# pcb_maquina.net
KiCad netlist of a schematic drawn in EAGLE
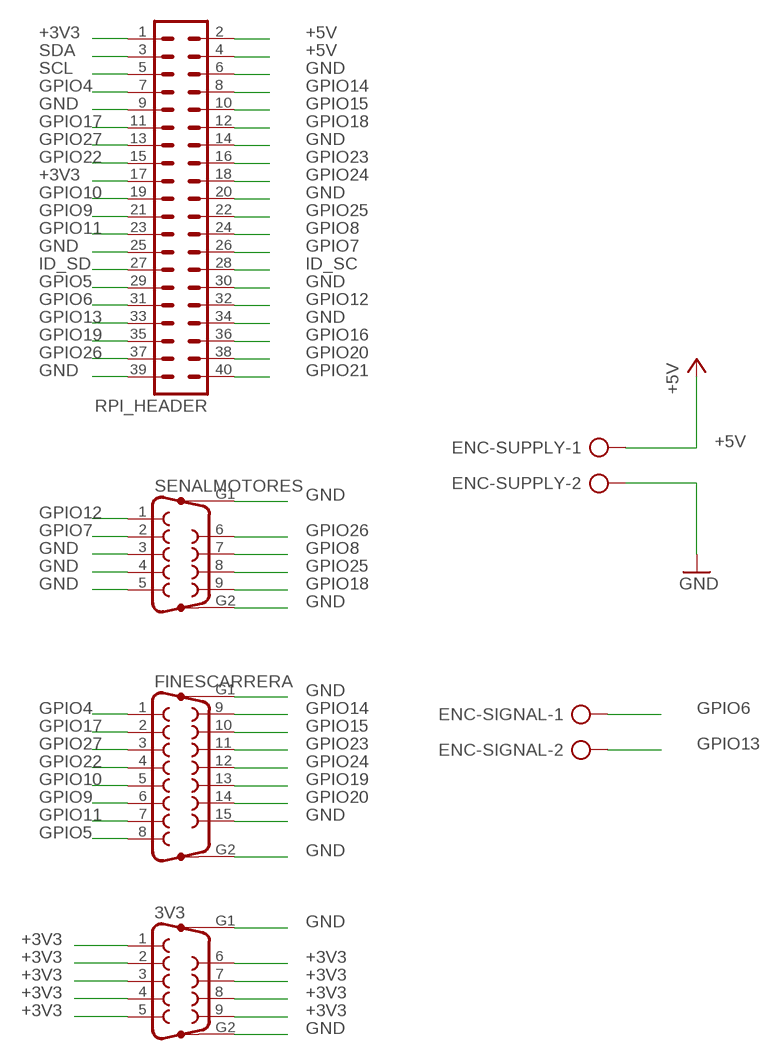
[diagram p0: schematic, sheet 1]
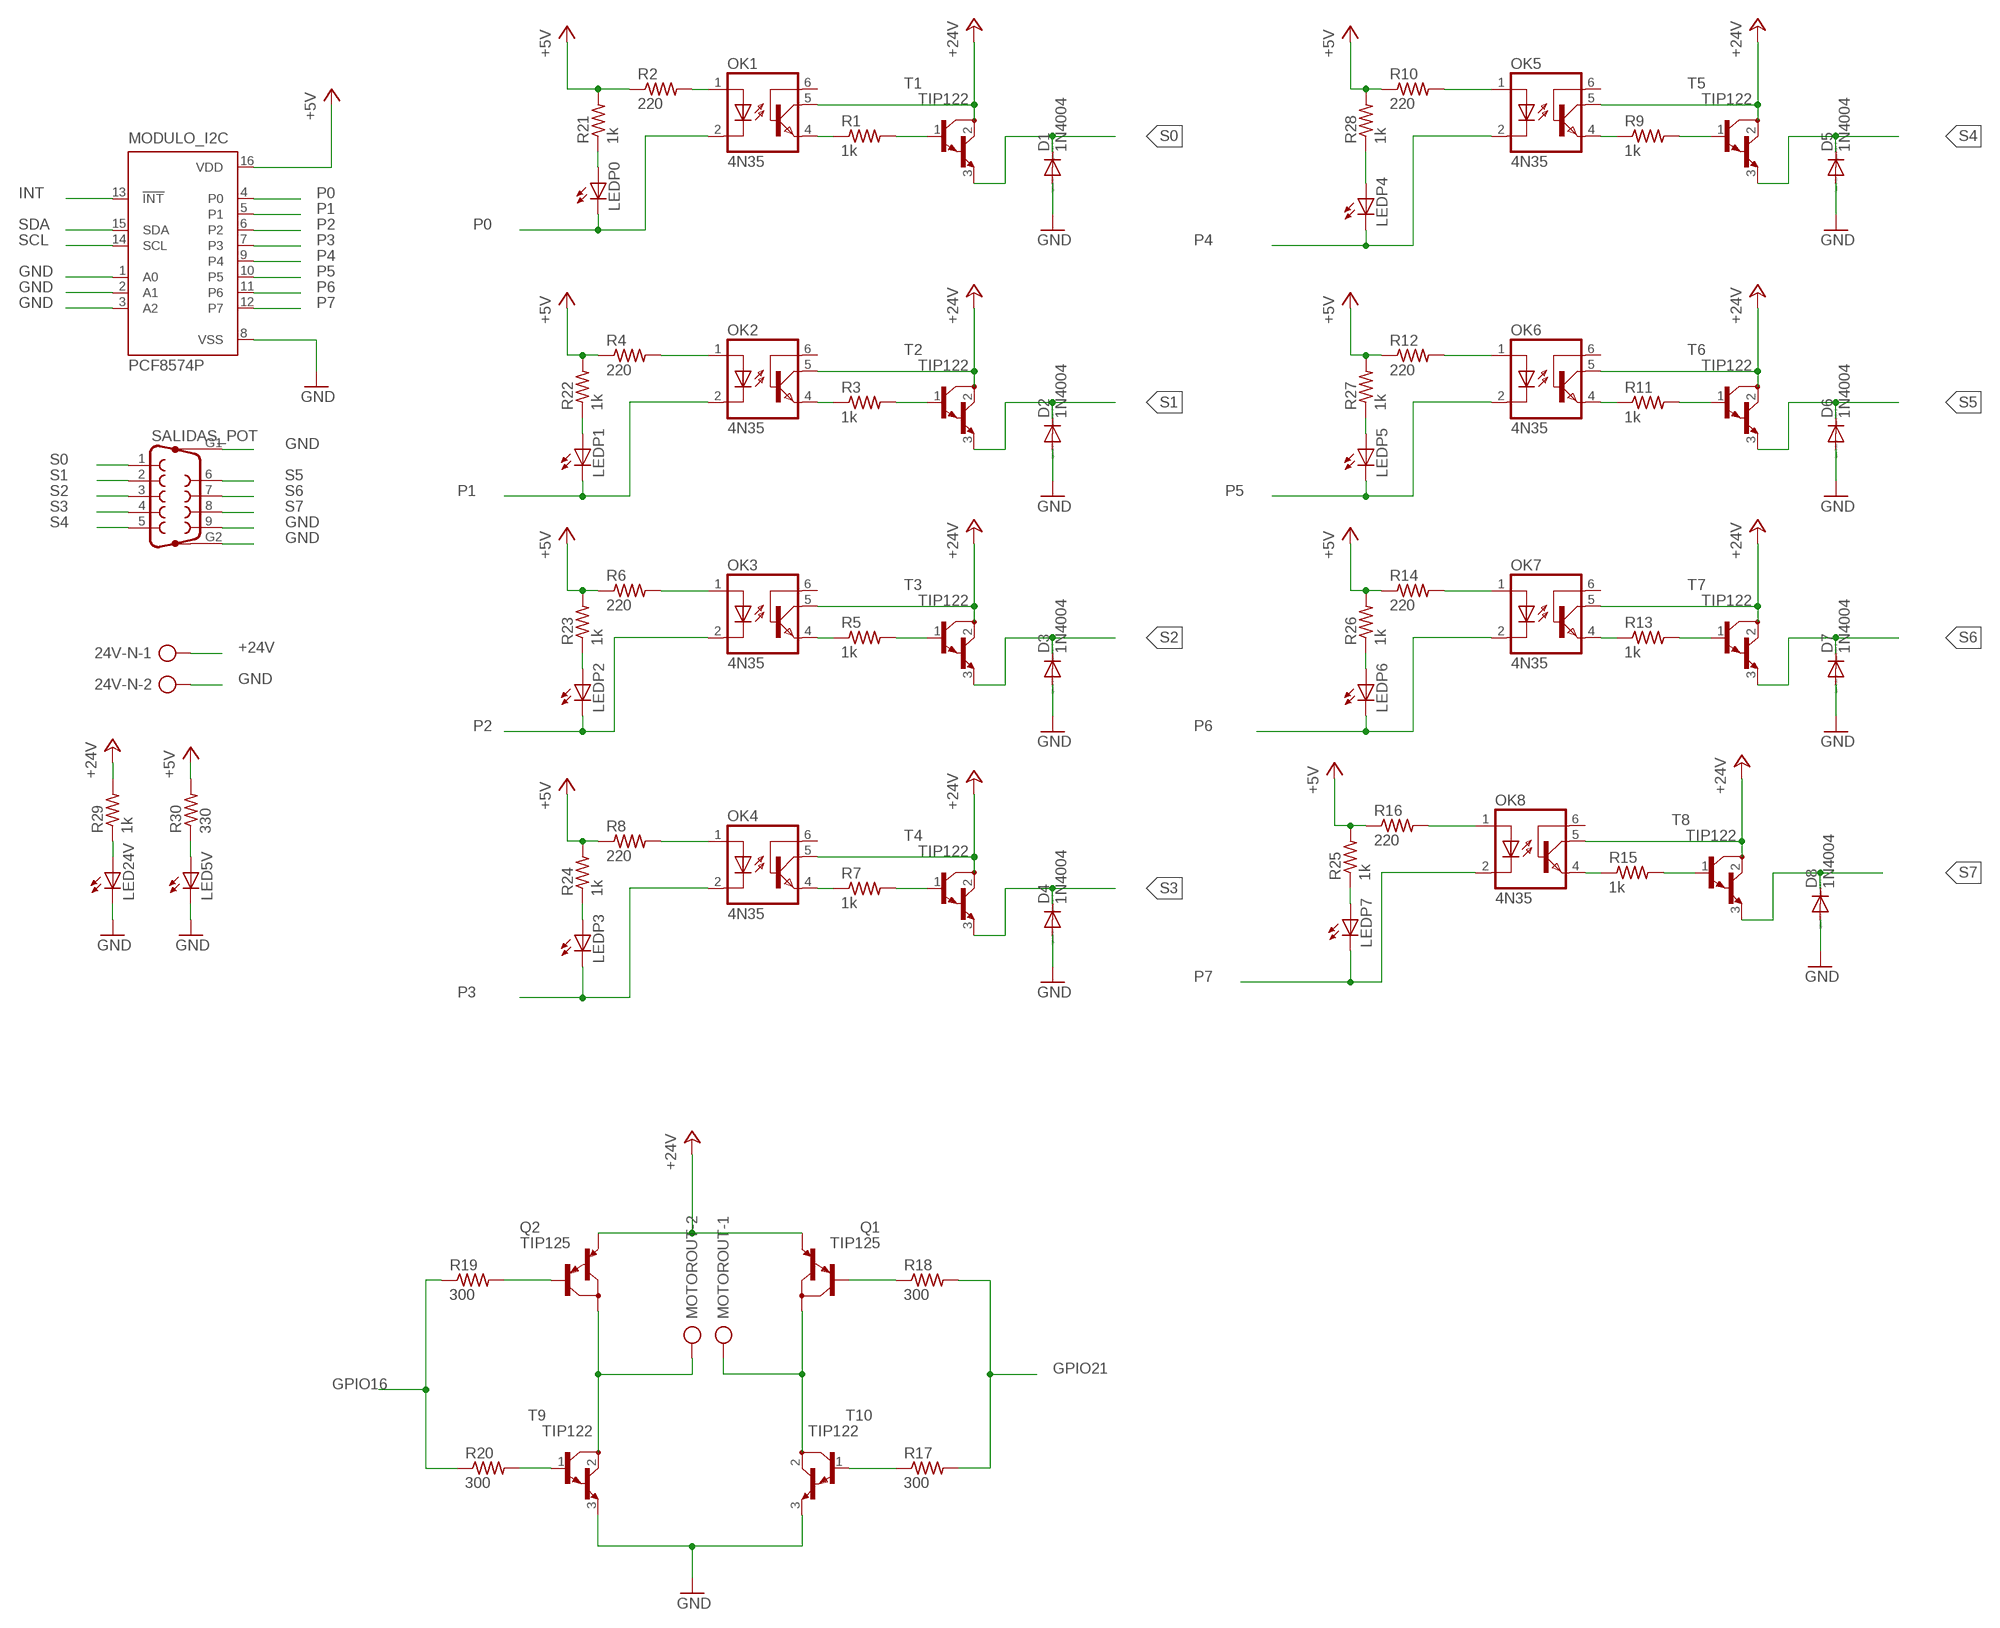
[diagram p1: schematic, sheet 2]

(export (version "E")
  (design (tool "Eeschema 10.0.6"))
  (components
    (comp (ref "3V3")
      (value "F09HP")
      (footprint "eagle-import:F09HP")
      (libsource (lib "eagle-import") (part "F09HP"))
    )
    (comp (ref "ENC-SIGNAL")
      (value "AK500/2")
      (footprint "eagle-import:AK500_2")
      (libsource (lib "eagle-import") (part "AK500/2"))
    )
    (comp (ref "ENC-SUPPLY")
      (value "AK500/2")
      (footprint "eagle-import:AK500_2")
      (libsource (lib "eagle-import") (part "AK500/2"))
    )
    (comp (ref "FINESCARRERA")
      (value "F15HP")
      (footprint "eagle-import:F15HP")
      (libsource (lib "eagle-import") (part "F15HP"))
    )
    (comp (ref "RPI_HEADER")
      (value "MA20-2")
      (footprint "eagle-import:MA20-2")
      (libsource (lib "eagle-import") (part "MA20-2"))
    )
    (comp (ref "SENALMOTORES")
      (value "F09HP")
      (footprint "eagle-import:F09HP")
      (libsource (lib "eagle-import") (part "F09HP"))
    )
    (comp (ref "24V-N")
      (value "AK300/2")
      (footprint "eagle-import:AK300_2")
      (libsource (lib "eagle-import") (part "AK300/2"))
    )
    (comp (ref "D1")
      (value "1N4004")
      (footprint "eagle-import:DO41-10")
      (libsource (lib "eagle-import") (part "1N4004"))
    )
    (comp (ref "D2")
      (value "1N4004")
      (footprint "eagle-import:DO41-10")
      (libsource (lib "eagle-import") (part "1N4004"))
    )
    (comp (ref "D3")
      (value "1N4004")
      (footprint "eagle-import:DO41-10")
      (libsource (lib "eagle-import") (part "1N4004"))
    )
    (comp (ref "D4")
      (value "1N4004")
      (footprint "eagle-import:DO41-10")
      (libsource (lib "eagle-import") (part "1N4004"))
    )
    (comp (ref "D5")
      (value "1N4004")
      (footprint "eagle-import:DO41-10")
      (libsource (lib "eagle-import") (part "1N4004"))
    )
    (comp (ref "D6")
      (value "1N4004")
      (footprint "eagle-import:DO41-10")
      (libsource (lib "eagle-import") (part "1N4004"))
    )
    (comp (ref "D7")
      (value "1N4004")
      (footprint "eagle-import:DO41-10")
      (libsource (lib "eagle-import") (part "1N4004"))
    )
    (comp (ref "D8")
      (value "1N4004")
      (footprint "eagle-import:DO41-10")
      (libsource (lib "eagle-import") (part "1N4004"))
    )
    (comp (ref "LED5V")
      (value "LED3MM")
      (footprint "eagle-import:LED3MM")
      (libsource (lib "eagle-import") (part "LED3MM"))
    )
    (comp (ref "LED24V")
      (value "LED3MM")
      (footprint "eagle-import:LED3MM")
      (libsource (lib "eagle-import") (part "LED3MM"))
    )
    (comp (ref "LEDP0")
      (value "LED3MM")
      (footprint "eagle-import:LED3MM")
      (libsource (lib "eagle-import") (part "LED3MM"))
    )
    (comp (ref "LEDP1")
      (value "LED3MM")
      (footprint "eagle-import:LED3MM")
      (libsource (lib "eagle-import") (part "LED3MM"))
    )
    (comp (ref "LEDP2")
      (value "LED3MM")
      (footprint "eagle-import:LED3MM")
      (libsource (lib "eagle-import") (part "LED3MM"))
    )
    (comp (ref "LEDP3")
      (value "LED3MM")
      (footprint "eagle-import:LED3MM")
      (libsource (lib "eagle-import") (part "LED3MM"))
    )
    (comp (ref "LEDP4")
      (value "LED3MM")
      (footprint "eagle-import:LED3MM")
      (libsource (lib "eagle-import") (part "LED3MM"))
    )
    (comp (ref "LEDP5")
      (value "LED3MM")
      (footprint "eagle-import:LED3MM")
      (libsource (lib "eagle-import") (part "LED3MM"))
    )
    (comp (ref "LEDP6")
      (value "LED3MM")
      (footprint "eagle-import:LED3MM")
      (libsource (lib "eagle-import") (part "LED3MM"))
    )
    (comp (ref "LEDP7")
      (value "LED3MM")
      (footprint "eagle-import:LED3MM")
      (libsource (lib "eagle-import") (part "LED3MM"))
    )
    (comp (ref "MODULO_I2C")
      (value "PCF8574P")
      (footprint "eagle-import:DIL16")
      (fields (field (name "MPN") "PCF8574PN"))
      (libsource (lib "eagle-import") (part "PCF8574P"))
    )
    (comp (ref "MOTOROUT")
      (value "AK300/2")
      (footprint "eagle-import:AK300_2")
      (libsource (lib "eagle-import") (part "AK300/2"))
    )
    (comp (ref "OK1")
      (value "4N35")
      (footprint "eagle-import:DIL06")
      (fields (field (name "MF") "FAIRCHILD SEMICONDUCTOR"))
      (libsource (lib "eagle-import") (part "4N35"))
    )
    (comp (ref "OK2")
      (value "4N35")
      (footprint "eagle-import:DIL06")
      (fields (field (name "MF") "FAIRCHILD SEMICONDUCTOR"))
      (libsource (lib "eagle-import") (part "4N35"))
    )
    (comp (ref "OK3")
      (value "4N35")
      (footprint "eagle-import:DIL06")
      (fields (field (name "MF") "FAIRCHILD SEMICONDUCTOR"))
      (libsource (lib "eagle-import") (part "4N35"))
    )
    (comp (ref "OK4")
      (value "4N35")
      (footprint "eagle-import:DIL06")
      (fields (field (name "MF") "FAIRCHILD SEMICONDUCTOR"))
      (libsource (lib "eagle-import") (part "4N35"))
    )
    (comp (ref "OK5")
      (value "4N35")
      (footprint "eagle-import:DIL06")
      (fields (field (name "MF") "FAIRCHILD SEMICONDUCTOR"))
      (libsource (lib "eagle-import") (part "4N35"))
    )
    (comp (ref "OK6")
      (value "4N35")
      (footprint "eagle-import:DIL06")
      (fields (field (name "MF") "FAIRCHILD SEMICONDUCTOR"))
      (libsource (lib "eagle-import") (part "4N35"))
    )
    (comp (ref "OK7")
      (value "4N35")
      (footprint "eagle-import:DIL06")
      (fields (field (name "MF") "FAIRCHILD SEMICONDUCTOR"))
      (libsource (lib "eagle-import") (part "4N35"))
    )
    (comp (ref "OK8")
      (value "4N35")
      (footprint "eagle-import:DIL06")
      (fields (field (name "MF") "FAIRCHILD SEMICONDUCTOR"))
      (libsource (lib "eagle-import") (part "4N35"))
    )
    (comp (ref "Q1")
      (value "TIP125")
      (footprint "eagle-import:TO220")
      (libsource (lib "eagle-import") (part "TIP125"))
    )
    (comp (ref "Q2")
      (value "TIP125")
      (footprint "eagle-import:TO220")
      (libsource (lib "eagle-import") (part "TIP125"))
    )
    (comp (ref "R1")
      (value "1k")
      (footprint "eagle-import:0204_7")
      (libsource (lib "eagle-import") (part "R-US_0204/7"))
    )
    (comp (ref "R2")
      (value "220")
      (footprint "eagle-import:0204_7")
      (libsource (lib "eagle-import") (part "R-US_0204/7"))
    )
    (comp (ref "R3")
      (value "1k")
      (footprint "eagle-import:0204_7")
      (libsource (lib "eagle-import") (part "R-US_0204/7"))
    )
    (comp (ref "R4")
      (value "220")
      (footprint "eagle-import:0204_7")
      (libsource (lib "eagle-import") (part "R-US_0204/7"))
    )
    (comp (ref "R5")
      (value "1k")
      (footprint "eagle-import:0204_7")
      (libsource (lib "eagle-import") (part "R-US_0204/7"))
    )
    (comp (ref "R6")
      (value "220")
      (footprint "eagle-import:0204_7")
      (libsource (lib "eagle-import") (part "R-US_0204/7"))
    )
    (comp (ref "R7")
      (value "1k")
      (footprint "eagle-import:0204_7")
      (libsource (lib "eagle-import") (part "R-US_0204/7"))
    )
    (comp (ref "R8")
      (value "220")
      (footprint "eagle-import:0204_7")
      (libsource (lib "eagle-import") (part "R-US_0204/7"))
    )
    (comp (ref "R9")
      (value "1k")
      (footprint "eagle-import:0204_7")
      (libsource (lib "eagle-import") (part "R-US_0204/7"))
    )
    (comp (ref "R10")
      (value "220")
      (footprint "eagle-import:0204_7")
      (libsource (lib "eagle-import") (part "R-US_0204/7"))
    )
    (comp (ref "R11")
      (value "1k")
      (footprint "eagle-import:0204_7")
      (libsource (lib "eagle-import") (part "R-US_0204/7"))
    )
    (comp (ref "R12")
      (value "220")
      (footprint "eagle-import:0204_7")
      (libsource (lib "eagle-import") (part "R-US_0204/7"))
    )
    (comp (ref "R13")
      (value "1k")
      (footprint "eagle-import:0204_7")
      (libsource (lib "eagle-import") (part "R-US_0204/7"))
    )
    (comp (ref "R14")
      (value "220")
      (footprint "eagle-import:0204_7")
      (libsource (lib "eagle-import") (part "R-US_0204/7"))
    )
    (comp (ref "R15")
      (value "1k")
      (footprint "eagle-import:0204_7")
      (libsource (lib "eagle-import") (part "R-US_0204/7"))
    )
    (comp (ref "R16")
      (value "220")
      (footprint "eagle-import:0204_7")
      (libsource (lib "eagle-import") (part "R-US_0204/7"))
    )
    (comp (ref "R17")
      (value "300")
      (footprint "eagle-import:0204_7")
      (libsource (lib "eagle-import") (part "R-US_0204/7"))
    )
    (comp (ref "R18")
      (value "300")
      (footprint "eagle-import:0204_7")
      (libsource (lib "eagle-import") (part "R-US_0204/7"))
    )
    (comp (ref "R19")
      (value "300")
      (footprint "eagle-import:0204_7")
      (libsource (lib "eagle-import") (part "R-US_0204/7"))
    )
    (comp (ref "R20")
      (value "300")
      (footprint "eagle-import:0204_7")
      (libsource (lib "eagle-import") (part "R-US_0204/7"))
    )
    (comp (ref "R21")
      (value "1k")
      (footprint "eagle-import:0204_7")
      (libsource (lib "eagle-import") (part "R-US_0204/7"))
    )
    (comp (ref "R22")
      (value "1k")
      (footprint "eagle-import:0204_7")
      (libsource (lib "eagle-import") (part "R-US_0204/7"))
    )
    (comp (ref "R23")
      (value "1k")
      (footprint "eagle-import:0204_7")
      (libsource (lib "eagle-import") (part "R-US_0204/7"))
    )
    (comp (ref "R24")
      (value "1k")
      (footprint "eagle-import:0204_7")
      (libsource (lib "eagle-import") (part "R-US_0204/7"))
    )
    (comp (ref "R25")
      (value "1k")
      (footprint "eagle-import:0204_7")
      (libsource (lib "eagle-import") (part "R-US_0204/7"))
    )
    (comp (ref "R26")
      (value "1k")
      (footprint "eagle-import:0204_7")
      (libsource (lib "eagle-import") (part "R-US_0204/7"))
    )
    (comp (ref "R27")
      (value "1k")
      (footprint "eagle-import:0204_7")
      (libsource (lib "eagle-import") (part "R-US_0204/7"))
    )
    (comp (ref "R28")
      (value "1k")
      (footprint "eagle-import:0204_7")
      (libsource (lib "eagle-import") (part "R-US_0204/7"))
    )
    (comp (ref "R29")
      (value "1k")
      (footprint "eagle-import:0204_7")
      (libsource (lib "eagle-import") (part "R-US_0204/7"))
    )
    (comp (ref "R30")
      (value "330")
      (footprint "eagle-import:0204_7")
      (libsource (lib "eagle-import") (part "R-US_0204/7"))
    )
    (comp (ref "SALIDAS_POT")
      (value "F09HP")
      (footprint "eagle-import:F09HP")
      (libsource (lib "eagle-import") (part "F09HP"))
    )
    (comp (ref "T1")
      (value "TIP122")
      (footprint "eagle-import:TO220")
      (libsource (lib "eagle-import") (part "TIP122"))
    )
    (comp (ref "T2")
      (value "TIP122")
      (footprint "eagle-import:TO220")
      (libsource (lib "eagle-import") (part "TIP122"))
    )
    (comp (ref "T3")
      (value "TIP122")
      (footprint "eagle-import:TO220")
      (libsource (lib "eagle-import") (part "TIP122"))
    )
    (comp (ref "T4")
      (value "TIP122")
      (footprint "eagle-import:TO220")
      (libsource (lib "eagle-import") (part "TIP122"))
    )
    (comp (ref "T5")
      (value "TIP122")
      (footprint "eagle-import:TO220")
      (libsource (lib "eagle-import") (part "TIP122"))
    )
    (comp (ref "T6")
      (value "TIP122")
      (footprint "eagle-import:TO220")
      (libsource (lib "eagle-import") (part "TIP122"))
    )
    (comp (ref "T7")
      (value "TIP122")
      (footprint "eagle-import:TO220")
      (libsource (lib "eagle-import") (part "TIP122"))
    )
    (comp (ref "T8")
      (value "TIP122")
      (footprint "eagle-import:TO220")
      (libsource (lib "eagle-import") (part "TIP122"))
    )
    (comp (ref "T9")
      (value "TIP122")
      (footprint "eagle-import:TO220")
      (libsource (lib "eagle-import") (part "TIP122"))
    )
    (comp (ref "T10")
      (value "TIP122")
      (footprint "eagle-import:TO220")
      (libsource (lib "eagle-import") (part "TIP122"))
    )
  )
  (nets
    (net (code "1") (name "+3V3") (class "Default")
      (node (ref "3V3") (pin "1") (pinfunction "1_1") (pintype "passive"))
      (node (ref "3V3") (pin "2") (pinfunction "2_2") (pintype "passive"))
      (node (ref "3V3") (pin "3") (pinfunction "3_3") (pintype "passive"))
      (node (ref "3V3") (pin "4") (pinfunction "4_4") (pintype "passive"))
      (node (ref "3V3") (pin "5") (pinfunction "5_5") (pintype "passive"))
      (node (ref "3V3") (pin "6") (pinfunction "6_6") (pintype "passive"))
      (node (ref "3V3") (pin "7") (pinfunction "7_7") (pintype "passive"))
      (node (ref "3V3") (pin "8") (pinfunction "8_8") (pintype "passive"))
      (node (ref "3V3") (pin "9") (pinfunction "9_9") (pintype "passive"))
      (node (ref "RPI_HEADER") (pin "1") (pinfunction "1_1") (pintype "passive"))
      (node (ref "RPI_HEADER") (pin "17") (pinfunction "17_17") (pintype "passive"))
    )
    (net (code "2") (name "+5V") (class "Default")
      (node (ref "ENC-SUPPLY") (pin "1") (pinfunction "KL_1") (pintype "passive"))
      (node (ref "MODULO_I2C") (pin "16") (pinfunction "VDD_16") (pintype "power_in"))
      (node (ref "R10") (pin "1") (pinfunction "1_1") (pintype "passive"))
      (node (ref "R12") (pin "1") (pinfunction "1_1") (pintype "passive"))
      (node (ref "R14") (pin "1") (pinfunction "1_1") (pintype "passive"))
      (node (ref "R16") (pin "1") (pinfunction "1_1") (pintype "passive"))
      (node (ref "R2") (pin "1") (pinfunction "1_1") (pintype "passive"))
      (node (ref "R21") (pin "2") (pinfunction "2_2") (pintype "passive"))
      (node (ref "R22") (pin "2") (pinfunction "2_2") (pintype "passive"))
      (node (ref "R23") (pin "2") (pinfunction "2_2") (pintype "passive"))
      (node (ref "R24") (pin "2") (pinfunction "2_2") (pintype "passive"))
      (node (ref "R25") (pin "2") (pinfunction "2_2") (pintype "passive"))
      (node (ref "R26") (pin "2") (pinfunction "2_2") (pintype "passive"))
      (node (ref "R27") (pin "2") (pinfunction "2_2") (pintype "passive"))
      (node (ref "R28") (pin "2") (pinfunction "2_2") (pintype "passive"))
      (node (ref "R30") (pin "2") (pinfunction "2_2") (pintype "passive"))
      (node (ref "R4") (pin "1") (pinfunction "1_1") (pintype "passive"))
      (node (ref "R6") (pin "1") (pinfunction "1_1") (pintype "passive"))
      (node (ref "R8") (pin "1") (pinfunction "1_1") (pintype "passive"))
      (node (ref "RPI_HEADER") (pin "2") (pinfunction "2_2") (pintype "passive"))
      (node (ref "RPI_HEADER") (pin "4") (pinfunction "4_4") (pintype "passive"))
    )
    (net (code "3") (name "+24V") (class "Default")
      (node (ref "24V-N") (pin "1") (pinfunction "KL_1") (pintype "passive"))
      (node (ref "OK1") (pin "5") (pinfunction "COL_5") (pintype "passive"))
      (node (ref "OK2") (pin "5") (pinfunction "COL_5") (pintype "passive"))
      (node (ref "OK3") (pin "5") (pinfunction "COL_5") (pintype "passive"))
      (node (ref "OK4") (pin "5") (pinfunction "COL_5") (pintype "passive"))
      (node (ref "OK5") (pin "5") (pinfunction "COL_5") (pintype "passive"))
      (node (ref "OK6") (pin "5") (pinfunction "COL_5") (pintype "passive"))
      (node (ref "OK7") (pin "5") (pinfunction "COL_5") (pintype "passive"))
      (node (ref "OK8") (pin "5") (pinfunction "COL_5") (pintype "passive"))
      (node (ref "Q1") (pin "3") (pinfunction "E_3") (pintype "passive"))
      (node (ref "Q2") (pin "3") (pinfunction "E_3") (pintype "passive"))
      (node (ref "R29") (pin "2") (pinfunction "2_2") (pintype "passive"))
      (node (ref "T1") (pin "2") (pinfunction "C_2") (pintype "passive"))
      (node (ref "T2") (pin "2") (pinfunction "C_2") (pintype "passive"))
      (node (ref "T3") (pin "2") (pinfunction "C_2") (pintype "passive"))
      (node (ref "T4") (pin "2") (pinfunction "C_2") (pintype "passive"))
      (node (ref "T5") (pin "2") (pinfunction "C_2") (pintype "passive"))
      (node (ref "T6") (pin "2") (pinfunction "C_2") (pintype "passive"))
      (node (ref "T7") (pin "2") (pinfunction "C_2") (pintype "passive"))
      (node (ref "T8") (pin "2") (pinfunction "C_2") (pintype "passive"))
    )
    (net (code "4") (name "GND") (class "Default")
      (node (ref "24V-N") (pin "2") (pinfunction "KL_2") (pintype "passive"))
      (node (ref "3V3") (pin "G1") (pinfunction "G1_G1") (pintype "passive"))
      (node (ref "3V3") (pin "G2") (pinfunction "G2_G2") (pintype "passive"))
      (node (ref "D1") (pin "A") (pinfunction "A_A") (pintype "passive"))
      (node (ref "D2") (pin "A") (pinfunction "A_A") (pintype "passive"))
      (node (ref "D3") (pin "A") (pinfunction "A_A") (pintype "passive"))
      (node (ref "D4") (pin "A") (pinfunction "A_A") (pintype "passive"))
      (node (ref "D5") (pin "A") (pinfunction "A_A") (pintype "passive"))
      (node (ref "D6") (pin "A") (pinfunction "A_A") (pintype "passive"))
      (node (ref "D7") (pin "A") (pinfunction "A_A") (pintype "passive"))
      (node (ref "D8") (pin "A") (pinfunction "A_A") (pintype "passive"))
      (node (ref "ENC-SUPPLY") (pin "2") (pinfunction "KL_2") (pintype "passive"))
      (node (ref "FINESCARRERA") (pin "15") (pinfunction "15_15") (pintype "passive"))
      (node (ref "FINESCARRERA") (pin "G1") (pinfunction "G1_G1") (pintype "passive"))
      (node (ref "FINESCARRERA") (pin "G2") (pinfunction "G2_G2") (pintype "passive"))
      (node (ref "LED24V") (pin "K") (pinfunction "C_K") (pintype "passive"))
      (node (ref "LED5V") (pin "K") (pinfunction "C_K") (pintype "passive"))
      (node (ref "MODULO_I2C") (pin "1") (pinfunction "A0_1") (pintype "input"))
      (node (ref "MODULO_I2C") (pin "2") (pinfunction "A1_2") (pintype "input"))
      (node (ref "MODULO_I2C") (pin "3") (pinfunction "A2_3") (pintype "input"))
      (node (ref "MODULO_I2C") (pin "8") (pinfunction "VSS_8") (pintype "power_in"))
      (node (ref "RPI_HEADER") (pin "14") (pinfunction "14_14") (pintype "passive"))
      (node (ref "RPI_HEADER") (pin "20") (pinfunction "20_20") (pintype "passive"))
      (node (ref "RPI_HEADER") (pin "25") (pinfunction "25_25") (pintype "passive"))
      (node (ref "RPI_HEADER") (pin "30") (pinfunction "30_30") (pintype "passive"))
      (node (ref "RPI_HEADER") (pin "34") (pinfunction "34_34") (pintype "passive"))
      (node (ref "RPI_HEADER") (pin "39") (pinfunction "39_39") (pintype "passive"))
      (node (ref "RPI_HEADER") (pin "6") (pinfunction "6_6") (pintype "passive"))
      (node (ref "RPI_HEADER") (pin "9") (pinfunction "9_9") (pintype "passive"))
      (node (ref "SALIDAS_POT") (pin "9") (pinfunction "9_9") (pintype "passive"))
      (node (ref "SALIDAS_POT") (pin "G1") (pinfunction "G1_G1") (pintype "passive"))
      (node (ref "SALIDAS_POT") (pin "G2") (pinfunction "G2_G2") (pintype "passive"))
      (node (ref "SENALMOTORES") (pin "3") (pinfunction "3_3") (pintype "passive"))
      (node (ref "SENALMOTORES") (pin "4") (pinfunction "4_4") (pintype "passive"))
      (node (ref "SENALMOTORES") (pin "5") (pinfunction "5_5") (pintype "passive"))
      (node (ref "SENALMOTORES") (pin "G1") (pinfunction "G1_G1") (pintype "passive"))
      (node (ref "SENALMOTORES") (pin "G2") (pinfunction "G2_G2") (pintype "passive"))
      (node (ref "T10") (pin "3") (pinfunction "E_3") (pintype "passive"))
      (node (ref "T9") (pin "3") (pinfunction "E_3") (pintype "passive"))
    )
    (net (code "5") (name "GPIO4") (class "Default")
      (node (ref "FINESCARRERA") (pin "1") (pinfunction "1_1") (pintype "passive"))
      (node (ref "RPI_HEADER") (pin "7") (pinfunction "7_7") (pintype "passive"))
    )
    (net (code "6") (name "GPIO5") (class "Default")
      (node (ref "FINESCARRERA") (pin "8") (pinfunction "8_8") (pintype "passive"))
      (node (ref "RPI_HEADER") (pin "29") (pinfunction "29_29") (pintype "passive"))
    )
    (net (code "7") (name "GPIO6") (class "Default")
      (node (ref "ENC-SIGNAL") (pin "1") (pinfunction "KL_1") (pintype "passive"))
      (node (ref "RPI_HEADER") (pin "31") (pinfunction "31_31") (pintype "passive"))
    )
    (net (code "8") (name "GPIO7") (class "Default")
      (node (ref "RPI_HEADER") (pin "26") (pinfunction "26_26") (pintype "passive"))
      (node (ref "SENALMOTORES") (pin "2") (pinfunction "2_2") (pintype "passive"))
    )
    (net (code "9") (name "GPIO8") (class "Default")
      (node (ref "RPI_HEADER") (pin "24") (pinfunction "24_24") (pintype "passive"))
      (node (ref "SENALMOTORES") (pin "7") (pinfunction "7_7") (pintype "passive"))
    )
    (net (code "10") (name "GPIO9") (class "Default")
      (node (ref "FINESCARRERA") (pin "6") (pinfunction "6_6") (pintype "passive"))
      (node (ref "RPI_HEADER") (pin "21") (pinfunction "21_21") (pintype "passive"))
    )
    (net (code "11") (name "GPIO10") (class "Default")
      (node (ref "FINESCARRERA") (pin "5") (pinfunction "5_5") (pintype "passive"))
      (node (ref "RPI_HEADER") (pin "19") (pinfunction "19_19") (pintype "passive"))
    )
    (net (code "12") (name "GPIO11") (class "Default")
      (node (ref "FINESCARRERA") (pin "7") (pinfunction "7_7") (pintype "passive"))
      (node (ref "RPI_HEADER") (pin "23") (pinfunction "23_23") (pintype "passive"))
    )
    (net (code "13") (name "GPIO12") (class "Default")
      (node (ref "RPI_HEADER") (pin "32") (pinfunction "32_32") (pintype "passive"))
      (node (ref "SENALMOTORES") (pin "1") (pinfunction "1_1") (pintype "passive"))
    )
    (net (code "14") (name "GPIO13") (class "Default")
      (node (ref "ENC-SIGNAL") (pin "2") (pinfunction "KL_2") (pintype "passive"))
      (node (ref "RPI_HEADER") (pin "33") (pinfunction "33_33") (pintype "passive"))
    )
    (net (code "15") (name "GPIO14") (class "Default")
      (node (ref "FINESCARRERA") (pin "9") (pinfunction "9_9") (pintype "passive"))
      (node (ref "RPI_HEADER") (pin "8") (pinfunction "8_8") (pintype "passive"))
    )
    (net (code "16") (name "GPIO15") (class "Default")
      (node (ref "FINESCARRERA") (pin "10") (pinfunction "10_10") (pintype "passive"))
      (node (ref "RPI_HEADER") (pin "10") (pinfunction "10_10") (pintype "passive"))
    )
    (net (code "17") (name "GPIO16") (class "Default")
      (node (ref "R19") (pin "1") (pinfunction "1_1") (pintype "passive"))
      (node (ref "R20") (pin "1") (pinfunction "1_1") (pintype "passive"))
      (node (ref "RPI_HEADER") (pin "36") (pinfunction "36_36") (pintype "passive"))
    )
    (net (code "18") (name "GPIO17") (class "Default")
      (node (ref "FINESCARRERA") (pin "2") (pinfunction "2_2") (pintype "passive"))
      (node (ref "RPI_HEADER") (pin "11") (pinfunction "11_11") (pintype "passive"))
    )
    (net (code "19") (name "GPIO18") (class "Default")
      (node (ref "RPI_HEADER") (pin "12") (pinfunction "12_12") (pintype "passive"))
      (node (ref "SENALMOTORES") (pin "9") (pinfunction "9_9") (pintype "passive"))
    )
    (net (code "20") (name "GPIO19") (class "Default")
      (node (ref "FINESCARRERA") (pin "13") (pinfunction "13_13") (pintype "passive"))
      (node (ref "RPI_HEADER") (pin "35") (pinfunction "35_35") (pintype "passive"))
    )
    (net (code "21") (name "GPIO20") (class "Default")
      (node (ref "FINESCARRERA") (pin "14") (pinfunction "14_14") (pintype "passive"))
      (node (ref "RPI_HEADER") (pin "38") (pinfunction "38_38") (pintype "passive"))
    )
    (net (code "22") (name "GPIO21") (class "Default")
      (node (ref "R17") (pin "2") (pinfunction "2_2") (pintype "passive"))
      (node (ref "R18") (pin "2") (pinfunction "2_2") (pintype "passive"))
      (node (ref "RPI_HEADER") (pin "40") (pinfunction "40_40") (pintype "passive"))
    )
    (net (code "23") (name "GPIO22") (class "Default")
      (node (ref "FINESCARRERA") (pin "4") (pinfunction "4_4") (pintype "passive"))
      (node (ref "RPI_HEADER") (pin "15") (pinfunction "15_15") (pintype "passive"))
    )
    (net (code "24") (name "GPIO23") (class "Default")
      (node (ref "FINESCARRERA") (pin "11") (pinfunction "11_11") (pintype "passive"))
      (node (ref "RPI_HEADER") (pin "16") (pinfunction "16_16") (pintype "passive"))
    )
    (net (code "25") (name "GPIO24") (class "Default")
      (node (ref "FINESCARRERA") (pin "12") (pinfunction "12_12") (pintype "passive"))
      (node (ref "RPI_HEADER") (pin "18") (pinfunction "18_18") (pintype "passive"))
    )
    (net (code "26") (name "GPIO25") (class "Default")
      (node (ref "RPI_HEADER") (pin "22") (pinfunction "22_22") (pintype "passive"))
      (node (ref "SENALMOTORES") (pin "8") (pinfunction "8_8") (pintype "passive"))
    )
    (net (code "27") (name "GPIO26") (class "Default")
      (node (ref "RPI_HEADER") (pin "37") (pinfunction "37_37") (pintype "passive"))
      (node (ref "SENALMOTORES") (pin "6") (pinfunction "6_6") (pintype "passive"))
    )
    (net (code "28") (name "GPIO27") (class "Default")
      (node (ref "FINESCARRERA") (pin "3") (pinfunction "3_3") (pintype "passive"))
      (node (ref "RPI_HEADER") (pin "13") (pinfunction "13_13") (pintype "passive"))
    )
    (net (code "29") (name "ID_SC") (class "Default")
      (node (ref "RPI_HEADER") (pin "28") (pinfunction "28_28") (pintype "passive"))
    )
    (net (code "30") (name "ID_SD") (class "Default")
      (node (ref "RPI_HEADER") (pin "27") (pinfunction "27_27") (pintype "passive"))
    )
    (net (code "31") (name "INT") (class "Default")
      (node (ref "MODULO_I2C") (pin "13") (pinfunction "~{INT}_13") (pintype "output"))
    )
    (net (code "32") (name "Net-(LED5V-PadA)") (class "Default")
      (node (ref "LED5V") (pin "A") (pinfunction "A_A") (pintype "passive"))
      (node (ref "R30") (pin "1") (pinfunction "1_1") (pintype "passive"))
    )
    (net (code "33") (name "Net-(LED24V-PadA)") (class "Default")
      (node (ref "LED24V") (pin "A") (pinfunction "A_A") (pintype "passive"))
      (node (ref "R29") (pin "1") (pinfunction "1_1") (pintype "passive"))
    )
    (net (code "34") (name "Net-(LEDP0-PadA)") (class "Default")
      (node (ref "LEDP0") (pin "A") (pinfunction "A_A") (pintype "passive"))
      (node (ref "R21") (pin "1") (pinfunction "1_1") (pintype "passive"))
    )
    (net (code "35") (name "Net-(LEDP1-PadA)") (class "Default")
      (node (ref "LEDP1") (pin "A") (pinfunction "A_A") (pintype "passive"))
      (node (ref "R22") (pin "1") (pinfunction "1_1") (pintype "passive"))
    )
    (net (code "36") (name "Net-(LEDP2-PadA)") (class "Default")
      (node (ref "LEDP2") (pin "A") (pinfunction "A_A") (pintype "passive"))
      (node (ref "R23") (pin "1") (pinfunction "1_1") (pintype "passive"))
    )
    (net (code "37") (name "Net-(LEDP3-PadA)") (class "Default")
      (node (ref "LEDP3") (pin "A") (pinfunction "A_A") (pintype "passive"))
      (node (ref "R24") (pin "1") (pinfunction "1_1") (pintype "passive"))
    )
    (net (code "38") (name "Net-(LEDP4-PadA)") (class "Default")
      (node (ref "LEDP4") (pin "A") (pinfunction "A_A") (pintype "passive"))
      (node (ref "R28") (pin "1") (pinfunction "1_1") (pintype "passive"))
    )
    (net (code "39") (name "Net-(LEDP5-PadA)") (class "Default")
      (node (ref "LEDP5") (pin "A") (pinfunction "A_A") (pintype "passive"))
      (node (ref "R27") (pin "1") (pinfunction "1_1") (pintype "passive"))
    )
    (net (code "40") (name "Net-(LEDP6-PadA)") (class "Default")
      (node (ref "LEDP6") (pin "A") (pinfunction "A_A") (pintype "passive"))
      (node (ref "R26") (pin "1") (pinfunction "1_1") (pintype "passive"))
    )
    (net (code "41") (name "Net-(LEDP7-PadA)") (class "Default")
      (node (ref "LEDP7") (pin "A") (pinfunction "A_A") (pintype "passive"))
      (node (ref "R25") (pin "1") (pinfunction "1_1") (pintype "passive"))
    )
    (net (code "42") (name "Net-(MOTOROUTA-KL)") (class "Default")
      (node (ref "MOTOROUT") (pin "1") (pinfunction "KL_1") (pintype "passive"))
      (node (ref "Q1") (pin "2") (pinfunction "C_2") (pintype "passive"))
      (node (ref "T10") (pin "2") (pinfunction "C_2") (pintype "passive"))
    )
    (net (code "43") (name "Net-(MOTOROUTB-KL)") (class "Default")
      (node (ref "MOTOROUT") (pin "2") (pinfunction "KL_2") (pintype "passive"))
      (node (ref "Q2") (pin "2") (pinfunction "C_2") (pintype "passive"))
      (node (ref "T9") (pin "2") (pinfunction "C_2") (pintype "passive"))
    )
    (net (code "44") (name "Net-(OK1-A)") (class "Default")
      (node (ref "OK1") (pin "1") (pinfunction "A_1") (pintype "passive"))
      (node (ref "R2") (pin "2") (pinfunction "2_2") (pintype "passive"))
    )
    (net (code "45") (name "Net-(OK1-EMI)") (class "Default")
      (node (ref "OK1") (pin "4") (pinfunction "EMI_4") (pintype "passive"))
      (node (ref "R1") (pin "1") (pinfunction "1_1") (pintype "passive"))
    )
    (net (code "46") (name "Net-(OK2-A)") (class "Default")
      (node (ref "OK2") (pin "1") (pinfunction "A_1") (pintype "passive"))
      (node (ref "R4") (pin "2") (pinfunction "2_2") (pintype "passive"))
    )
    (net (code "47") (name "Net-(OK2-EMI)") (class "Default")
      (node (ref "OK2") (pin "4") (pinfunction "EMI_4") (pintype "passive"))
      (node (ref "R3") (pin "1") (pinfunction "1_1") (pintype "passive"))
    )
    (net (code "48") (name "Net-(OK3-A)") (class "Default")
      (node (ref "OK3") (pin "1") (pinfunction "A_1") (pintype "passive"))
      (node (ref "R6") (pin "2") (pinfunction "2_2") (pintype "passive"))
    )
    (net (code "49") (name "Net-(OK3-EMI)") (class "Default")
      (node (ref "OK3") (pin "4") (pinfunction "EMI_4") (pintype "passive"))
      (node (ref "R5") (pin "1") (pinfunction "1_1") (pintype "passive"))
    )
    (net (code "50") (name "Net-(OK4-A)") (class "Default")
      (node (ref "OK4") (pin "1") (pinfunction "A_1") (pintype "passive"))
      (node (ref "R8") (pin "2") (pinfunction "2_2") (pintype "passive"))
    )
    (net (code "51") (name "Net-(OK4-EMI)") (class "Default")
      (node (ref "OK4") (pin "4") (pinfunction "EMI_4") (pintype "passive"))
      (node (ref "R7") (pin "1") (pinfunction "1_1") (pintype "passive"))
    )
    (net (code "52") (name "Net-(OK5-A)") (class "Default")
      (node (ref "OK5") (pin "1") (pinfunction "A_1") (pintype "passive"))
      (node (ref "R10") (pin "2") (pinfunction "2_2") (pintype "passive"))
    )
    (net (code "53") (name "Net-(OK5-EMI)") (class "Default")
      (node (ref "OK5") (pin "4") (pinfunction "EMI_4") (pintype "passive"))
      (node (ref "R9") (pin "1") (pinfunction "1_1") (pintype "passive"))
    )
    (net (code "54") (name "Net-(OK6-A)") (class "Default")
      (node (ref "OK6") (pin "1") (pinfunction "A_1") (pintype "passive"))
      (node (ref "R12") (pin "2") (pinfunction "2_2") (pintype "passive"))
    )
    (net (code "55") (name "Net-(OK6-EMI)") (class "Default")
      (node (ref "OK6") (pin "4") (pinfunction "EMI_4") (pintype "passive"))
      (node (ref "R11") (pin "1") (pinfunction "1_1") (pintype "passive"))
    )
    (net (code "56") (name "Net-(OK7-A)") (class "Default")
      (node (ref "OK7") (pin "1") (pinfunction "A_1") (pintype "passive"))
      (node (ref "R14") (pin "2") (pinfunction "2_2") (pintype "passive"))
    )
    (net (code "57") (name "Net-(OK7-EMI)") (class "Default")
      (node (ref "OK7") (pin "4") (pinfunction "EMI_4") (pintype "passive"))
      (node (ref "R13") (pin "1") (pinfunction "1_1") (pintype "passive"))
    )
    (net (code "58") (name "Net-(OK8-A)") (class "Default")
      (node (ref "OK8") (pin "1") (pinfunction "A_1") (pintype "passive"))
      (node (ref "R16") (pin "2") (pinfunction "2_2") (pintype "passive"))
    )
    (net (code "59") (name "Net-(OK8-EMI)") (class "Default")
      (node (ref "OK8") (pin "4") (pinfunction "EMI_4") (pintype "passive"))
      (node (ref "R15") (pin "1") (pinfunction "1_1") (pintype "passive"))
    )
    (net (code "60") (name "Net-(Q1-B)") (class "Default")
      (node (ref "Q1") (pin "1") (pinfunction "B_1") (pintype "passive"))
      (node (ref "R18") (pin "1") (pinfunction "1_1") (pintype "passive"))
    )
    (net (code "61") (name "Net-(Q2-B)") (class "Default")
      (node (ref "Q2") (pin "1") (pinfunction "B_1") (pintype "passive"))
      (node (ref "R19") (pin "2") (pinfunction "2_2") (pintype "passive"))
    )
    (net (code "62") (name "Net-(T1-B)") (class "Default")
      (node (ref "R1") (pin "2") (pinfunction "2_2") (pintype "passive"))
      (node (ref "T1") (pin "1") (pinfunction "B_1") (pintype "passive"))
    )
    (net (code "63") (name "Net-(T2-B)") (class "Default")
      (node (ref "R3") (pin "2") (pinfunction "2_2") (pintype "passive"))
      (node (ref "T2") (pin "1") (pinfunction "B_1") (pintype "passive"))
    )
    (net (code "64") (name "Net-(T3-B)") (class "Default")
      (node (ref "R5") (pin "2") (pinfunction "2_2") (pintype "passive"))
      (node (ref "T3") (pin "1") (pinfunction "B_1") (pintype "passive"))
    )
    (net (code "65") (name "Net-(T4-B)") (class "Default")
      (node (ref "R7") (pin "2") (pinfunction "2_2") (pintype "passive"))
      (node (ref "T4") (pin "1") (pinfunction "B_1") (pintype "passive"))
    )
    (net (code "66") (name "Net-(T5-B)") (class "Default")
      (node (ref "R9") (pin "2") (pinfunction "2_2") (pintype "passive"))
      (node (ref "T5") (pin "1") (pinfunction "B_1") (pintype "passive"))
    )
    (net (code "67") (name "Net-(T6-B)") (class "Default")
      (node (ref "R11") (pin "2") (pinfunction "2_2") (pintype "passive"))
      (node (ref "T6") (pin "1") (pinfunction "B_1") (pintype "passive"))
    )
    (net (code "68") (name "Net-(T7-B)") (class "Default")
      (node (ref "R13") (pin "2") (pinfunction "2_2") (pintype "passive"))
      (node (ref "T7") (pin "1") (pinfunction "B_1") (pintype "passive"))
    )
    (net (code "69") (name "Net-(T8-B)") (class "Default")
      (node (ref "R15") (pin "2") (pinfunction "2_2") (pintype "passive"))
      (node (ref "T8") (pin "1") (pinfunction "B_1") (pintype "passive"))
    )
    (net (code "70") (name "Net-(T9-B)") (class "Default")
      (node (ref "R20") (pin "2") (pinfunction "2_2") (pintype "passive"))
      (node (ref "T9") (pin "1") (pinfunction "B_1") (pintype "passive"))
    )
    (net (code "71") (name "Net-(T10-B)") (class "Default")
      (node (ref "R17") (pin "1") (pinfunction "1_1") (pintype "passive"))
      (node (ref "T10") (pin "1") (pinfunction "B_1") (pintype "passive"))
    )
    (net (code "72") (name "P0") (class "Default")
      (node (ref "LEDP0") (pin "K") (pinfunction "C_K") (pintype "passive"))
      (node (ref "MODULO_I2C") (pin "4") (pinfunction "P0_4") (pintype "bidirectional"))
      (node (ref "OK1") (pin "2") (pinfunction "C_2") (pintype "passive"))
    )
    (net (code "73") (name "P1") (class "Default")
      (node (ref "LEDP1") (pin "K") (pinfunction "C_K") (pintype "passive"))
      (node (ref "MODULO_I2C") (pin "5") (pinfunction "P1_5") (pintype "bidirectional"))
      (node (ref "OK2") (pin "2") (pinfunction "C_2") (pintype "passive"))
    )
    (net (code "74") (name "P2") (class "Default")
      (node (ref "LEDP2") (pin "K") (pinfunction "C_K") (pintype "passive"))
      (node (ref "MODULO_I2C") (pin "6") (pinfunction "P2_6") (pintype "bidirectional"))
      (node (ref "OK3") (pin "2") (pinfunction "C_2") (pintype "passive"))
    )
    (net (code "75") (name "P3") (class "Default")
      (node (ref "LEDP3") (pin "K") (pinfunction "C_K") (pintype "passive"))
      (node (ref "MODULO_I2C") (pin "7") (pinfunction "P3_7") (pintype "bidirectional"))
      (node (ref "OK4") (pin "2") (pinfunction "C_2") (pintype "passive"))
    )
    (net (code "76") (name "P4") (class "Default")
      (node (ref "LEDP4") (pin "K") (pinfunction "C_K") (pintype "passive"))
      (node (ref "MODULO_I2C") (pin "9") (pinfunction "P4_9") (pintype "bidirectional"))
      (node (ref "OK5") (pin "2") (pinfunction "C_2") (pintype "passive"))
    )
    (net (code "77") (name "P5") (class "Default")
      (node (ref "LEDP5") (pin "K") (pinfunction "C_K") (pintype "passive"))
      (node (ref "MODULO_I2C") (pin "10") (pinfunction "P5_10") (pintype "bidirectional"))
      (node (ref "OK6") (pin "2") (pinfunction "C_2") (pintype "passive"))
    )
    (net (code "78") (name "P6") (class "Default")
      (node (ref "LEDP6") (pin "K") (pinfunction "C_K") (pintype "passive"))
      (node (ref "MODULO_I2C") (pin "11") (pinfunction "P6_11") (pintype "bidirectional"))
      (node (ref "OK7") (pin "2") (pinfunction "C_2") (pintype "passive"))
    )
    (net (code "79") (name "P7") (class "Default")
      (node (ref "LEDP7") (pin "K") (pinfunction "C_K") (pintype "passive"))
      (node (ref "MODULO_I2C") (pin "12") (pinfunction "P7_12") (pintype "bidirectional"))
      (node (ref "OK8") (pin "2") (pinfunction "C_2") (pintype "passive"))
    )
    (net (code "80") (name "S0") (class "Default")
      (node (ref "D1") (pin "C") (pinfunction "C_C") (pintype "passive"))
      (node (ref "SALIDAS_POT") (pin "1") (pinfunction "1_1") (pintype "passive"))
      (node (ref "T1") (pin "3") (pinfunction "E_3") (pintype "passive"))
    )
    (net (code "81") (name "S1") (class "Default")
      (node (ref "D2") (pin "C") (pinfunction "C_C") (pintype "passive"))
      (node (ref "SALIDAS_POT") (pin "2") (pinfunction "2_2") (pintype "passive"))
      (node (ref "T2") (pin "3") (pinfunction "E_3") (pintype "passive"))
    )
    (net (code "82") (name "S2") (class "Default")
      (node (ref "D3") (pin "C") (pinfunction "C_C") (pintype "passive"))
      (node (ref "SALIDAS_POT") (pin "3") (pinfunction "3_3") (pintype "passive"))
      (node (ref "T3") (pin "3") (pinfunction "E_3") (pintype "passive"))
    )
    (net (code "83") (name "S3") (class "Default")
      (node (ref "D4") (pin "C") (pinfunction "C_C") (pintype "passive"))
      (node (ref "SALIDAS_POT") (pin "4") (pinfunction "4_4") (pintype "passive"))
      (node (ref "T4") (pin "3") (pinfunction "E_3") (pintype "passive"))
    )
    (net (code "84") (name "S4") (class "Default")
      (node (ref "D5") (pin "C") (pinfunction "C_C") (pintype "passive"))
      (node (ref "SALIDAS_POT") (pin "5") (pinfunction "5_5") (pintype "passive"))
      (node (ref "T5") (pin "3") (pinfunction "E_3") (pintype "passive"))
    )
    (net (code "85") (name "S5") (class "Default")
      (node (ref "D6") (pin "C") (pinfunction "C_C") (pintype "passive"))
      (node (ref "SALIDAS_POT") (pin "6") (pinfunction "6_6") (pintype "passive"))
      (node (ref "T6") (pin "3") (pinfunction "E_3") (pintype "passive"))
    )
    (net (code "86") (name "S6") (class "Default")
      (node (ref "D7") (pin "C") (pinfunction "C_C") (pintype "passive"))
      (node (ref "SALIDAS_POT") (pin "7") (pinfunction "7_7") (pintype "passive"))
      (node (ref "T7") (pin "3") (pinfunction "E_3") (pintype "passive"))
    )
    (net (code "87") (name "S7") (class "Default")
      (node (ref "D8") (pin "C") (pinfunction "C_C") (pintype "passive"))
      (node (ref "SALIDAS_POT") (pin "8") (pinfunction "8_8") (pintype "passive"))
      (node (ref "T8") (pin "3") (pinfunction "E_3") (pintype "passive"))
    )
    (net (code "88") (name "SCL") (class "Default")
      (node (ref "MODULO_I2C") (pin "14") (pinfunction "SCL_14") (pintype "input"))
      (node (ref "RPI_HEADER") (pin "5") (pinfunction "5_5") (pintype "passive"))
    )
    (net (code "89") (name "SDA") (class "Default")
      (node (ref "MODULO_I2C") (pin "15") (pinfunction "SDA_15") (pintype "bidirectional"))
      (node (ref "RPI_HEADER") (pin "3") (pinfunction "3_3") (pintype "passive"))
    )
    (net (code "90") (name "unconnected-(OK1-BAS-Pad6)") (class "Default")
      (node (ref "OK1") (pin "6") (pinfunction "BAS_6") (pintype "passive"))
    )
    (net (code "91") (name "unconnected-(OK2-BAS-Pad6)") (class "Default")
      (node (ref "OK2") (pin "6") (pinfunction "BAS_6") (pintype "passive"))
    )
    (net (code "92") (name "unconnected-(OK3-BAS-Pad6)") (class "Default")
      (node (ref "OK3") (pin "6") (pinfunction "BAS_6") (pintype "passive"))
    )
    (net (code "93") (name "unconnected-(OK4-BAS-Pad6)") (class "Default")
      (node (ref "OK4") (pin "6") (pinfunction "BAS_6") (pintype "passive"))
    )
    (net (code "94") (name "unconnected-(OK5-BAS-Pad6)") (class "Default")
      (node (ref "OK5") (pin "6") (pinfunction "BAS_6") (pintype "passive"))
    )
    (net (code "95") (name "unconnected-(OK6-BAS-Pad6)") (class "Default")
      (node (ref "OK6") (pin "6") (pinfunction "BAS_6") (pintype "passive"))
    )
    (net (code "96") (name "unconnected-(OK7-BAS-Pad6)") (class "Default")
      (node (ref "OK7") (pin "6") (pinfunction "BAS_6") (pintype "passive"))
    )
    (net (code "97") (name "unconnected-(OK8-BAS-Pad6)") (class "Default")
      (node (ref "OK8") (pin "6") (pinfunction "BAS_6") (pintype "passive"))
    )
  )
)
